# Sheet3.net
KiCad netlist of a schematic drawn in Altium Designer
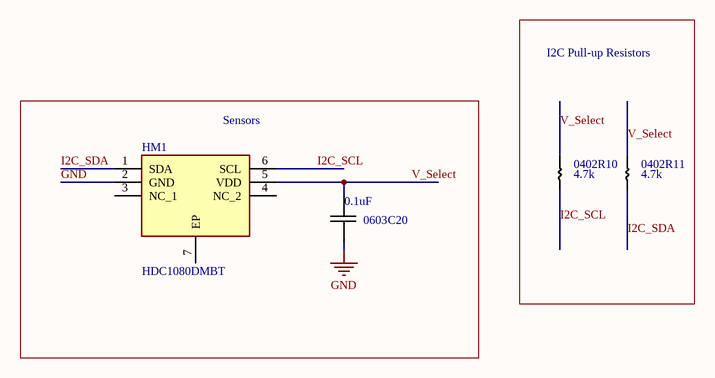
[diagram p0: Sheet3.SchDoc]

(export (version "E")
  (design (tool "Eeschema 10.0.6"))
  (components
    (comp (ref "C20")
      (value "0.1uF")
      (footprint "0603_SMD")
      (libsource (lib "Enviornmental_Sensor") (part "C_0603"))
    )
    (comp (ref "HM1")
      (value "HDC1080DMBT")
      (footprint "SON100P300X300X80-7N")
      (description "Hygrometer")
      (fields
        (field (name "MOUSER PART NUMBER") "595-HDC1080DMBT")
        (field (name "RS PART NUMBER") "1330170P")
      )
      (libsource (lib "EnvironmentalSensor") (part "HDC1080DMBT"))
    )
    (comp (ref "R10")
      (value "4.7k")
      (footprint "0402_SMD")
      (libsource (lib "Enviornmental_Sensor") (part "R_0402"))
    )
    (comp (ref "R11")
      (value "4.7k")
      (footprint "0402_SMD")
      (libsource (lib "Enviornmental_Sensor") (part "R_0402"))
    )
  )
  (nets
    (net (code "1") (name "/I2C_SCL") (class "Default")
      (node (ref "HM1") (pin "6") (pinfunction "SCL_6") (pintype "passive"))
      (node (ref "R10") (pin "2") (pinfunction "2_2") (pintype "passive"))
    )
    (net (code "2") (name "/I2C_SDA") (class "Default")
      (node (ref "HM1") (pin "1") (pinfunction "SDA_1") (pintype "passive"))
      (node (ref "R11") (pin "2") (pinfunction "2_2") (pintype "passive"))
    )
    (net (code "3") (name "/V_Select") (class "Default")
      (node (ref "C20") (pin "2") (pinfunction "2_2") (pintype "passive"))
      (node (ref "HM1") (pin "5") (pinfunction "VDD_5") (pintype "power_in"))
      (node (ref "R10") (pin "1") (pinfunction "1_1") (pintype "passive"))
      (node (ref "R11") (pin "1") (pinfunction "1_1") (pintype "passive"))
    )
    (net (code "4") (name "GND") (class "Default")
      (node (ref "C20") (pin "1") (pinfunction "1_1") (pintype "passive"))
      (node (ref "HM1") (pin "2") (pinfunction "GND_2") (pintype "power_in"))
    )
    (net (code "5") (name "unconnected-(HM1-EP-Pad7)") (class "Default")
      (node (ref "HM1") (pin "7") (pinfunction "EP_7") (pintype "power_in"))
    )
    (net (code "6") (name "unconnected-(HM1-NC_1-Pad3)") (class "Default")
      (node (ref "HM1") (pin "3") (pinfunction "NC_1_3") (pintype "passive"))
    )
    (net (code "7") (name "unconnected-(HM1-NC_2-Pad4)") (class "Default")
      (node (ref "HM1") (pin "4") (pinfunction "NC_2_4") (pintype "passive"))
    )
  )
)
